# fpga11-serdes-power.net
KiCad netlist of a schematic drawn in Altium Designer
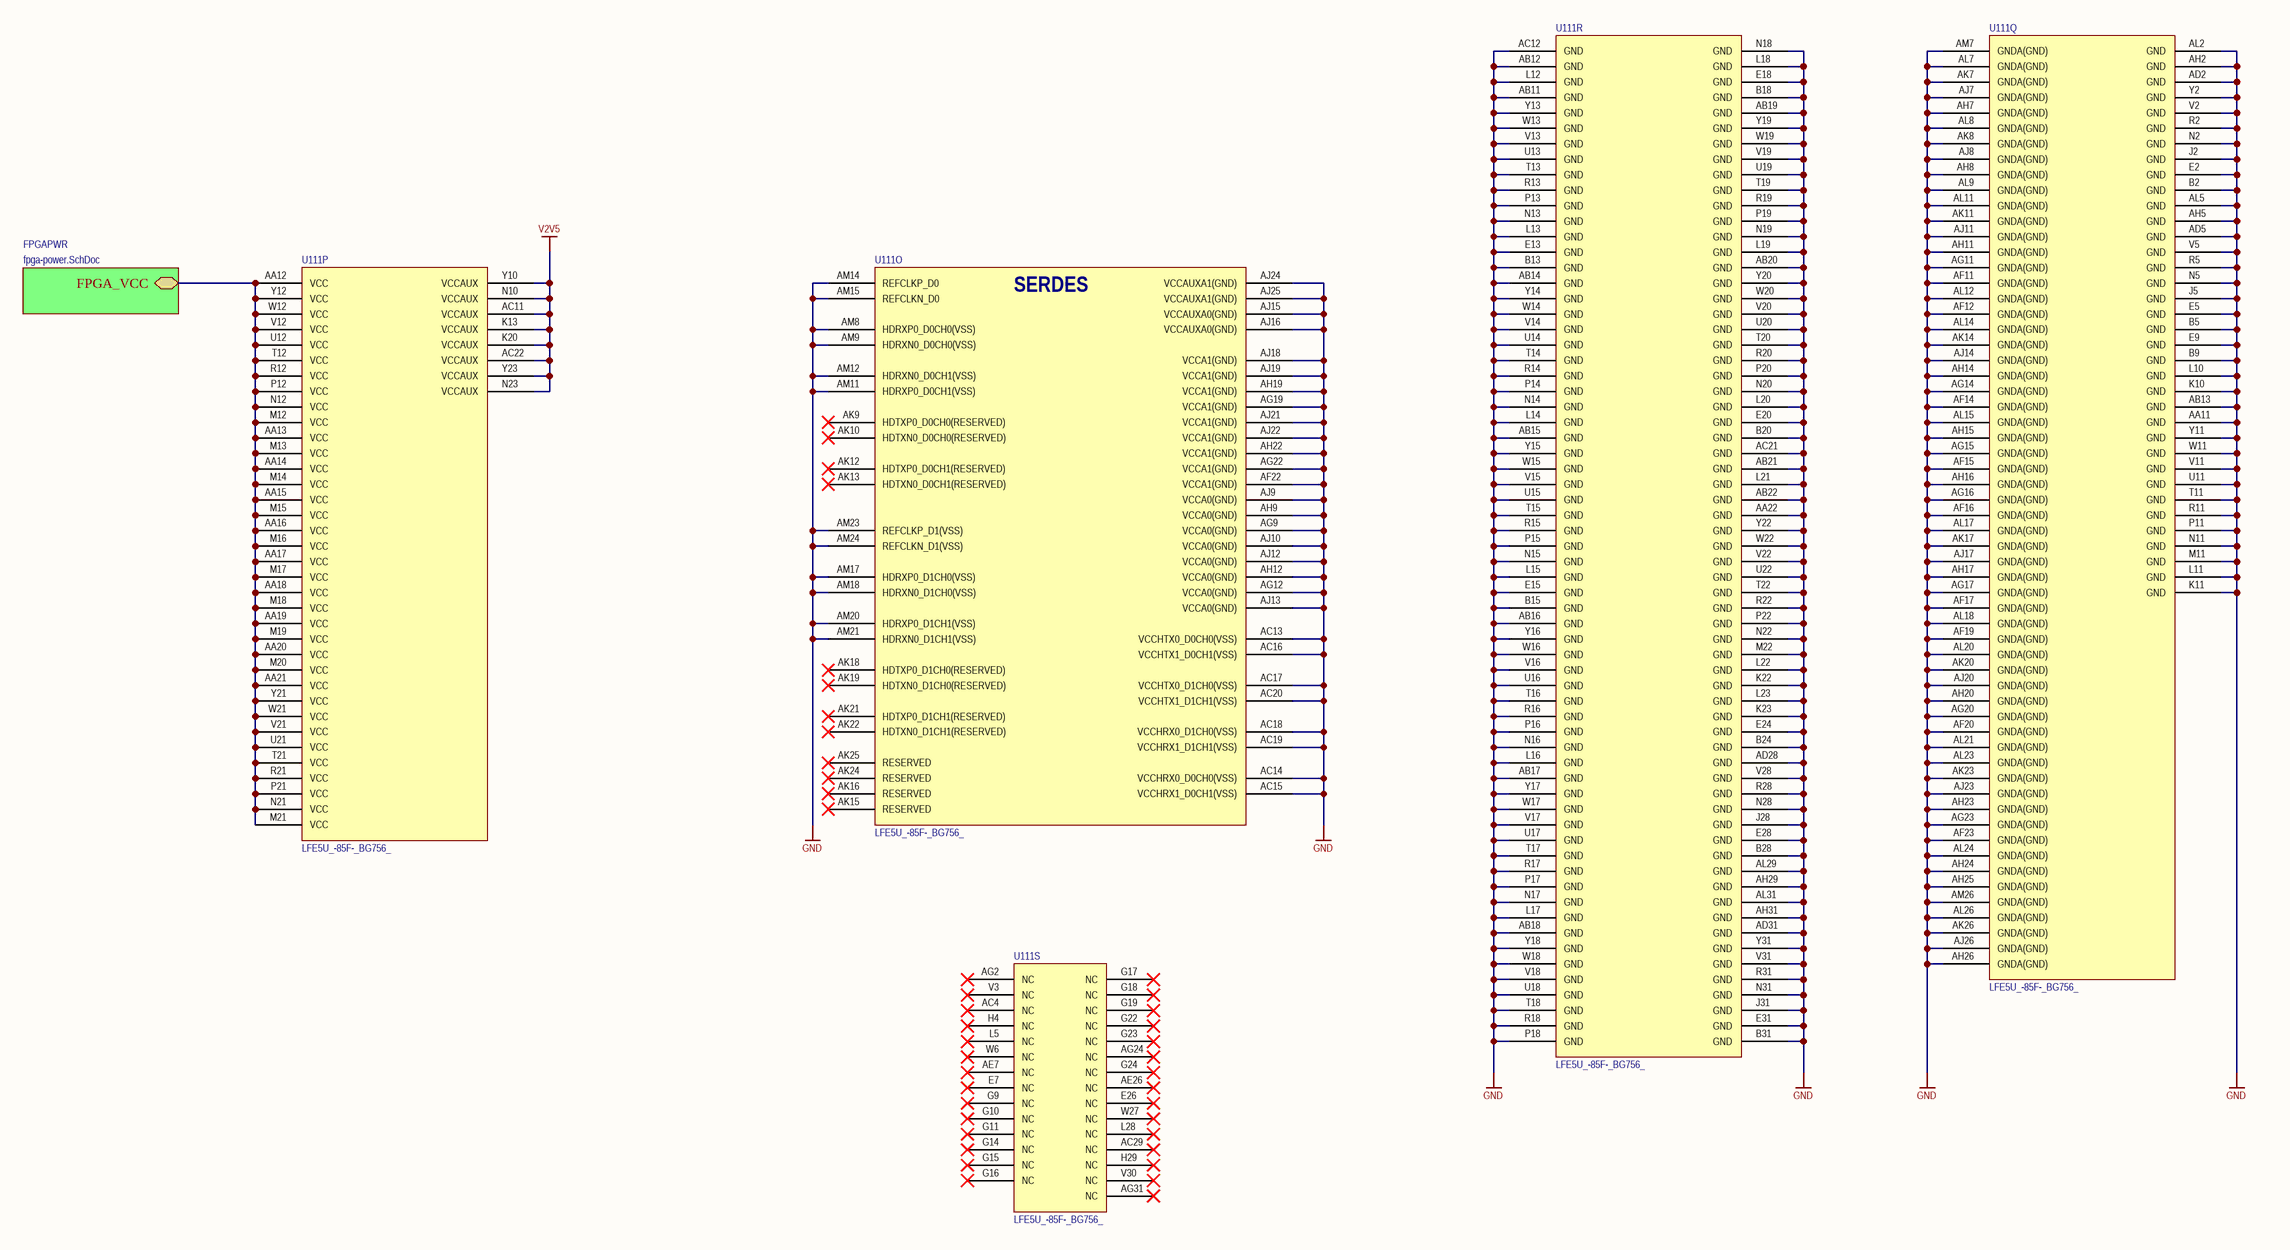
[diagram p0: fpga11-serdes-power.SchDoc]

(export (version "E")
  (design (tool "Eeschema 10.0.6"))
  (components
    (comp (ref "U111")
      (value "LFE5U_-85F-_BG756_")
      (footprint "lattice:caBGA756")
      (description "ECP5 FPGA, 85k LUT, 756-caBGA")
      (fields (field (name "MANUFACTURER") "Lattice Semiconductor"))
      (libsource (lib "lattice") (part "LFE5U_-85F-_BG756_"))
    )
  )
  (nets
    (net (code "1") (name "/FPGA_VCC") (class "Default")
      (node (ref "U111") (pin "AA12") (pinfunction "VCC_AA12") (pintype "power_in"))
      (node (ref "U111") (pin "AA13") (pinfunction "VCC_AA13") (pintype "power_in"))
      (node (ref "U111") (pin "AA14") (pinfunction "VCC_AA14") (pintype "power_in"))
      (node (ref "U111") (pin "AA15") (pinfunction "VCC_AA15") (pintype "power_in"))
      (node (ref "U111") (pin "AA16") (pinfunction "VCC_AA16") (pintype "power_in"))
      (node (ref "U111") (pin "AA17") (pinfunction "VCC_AA17") (pintype "power_in"))
      (node (ref "U111") (pin "AA18") (pinfunction "VCC_AA18") (pintype "power_in"))
      (node (ref "U111") (pin "AA19") (pinfunction "VCC_AA19") (pintype "power_in"))
      (node (ref "U111") (pin "AA20") (pinfunction "VCC_AA20") (pintype "power_in"))
      (node (ref "U111") (pin "AA21") (pinfunction "VCC_AA21") (pintype "power_in"))
      (node (ref "U111") (pin "M12") (pinfunction "VCC_M12") (pintype "power_in"))
      (node (ref "U111") (pin "M13") (pinfunction "VCC_M13") (pintype "power_in"))
      (node (ref "U111") (pin "M14") (pinfunction "VCC_M14") (pintype "power_in"))
      (node (ref "U111") (pin "M15") (pinfunction "VCC_M15") (pintype "power_in"))
      (node (ref "U111") (pin "M16") (pinfunction "VCC_M16") (pintype "power_in"))
      (node (ref "U111") (pin "M17") (pinfunction "VCC_M17") (pintype "power_in"))
      (node (ref "U111") (pin "M18") (pinfunction "VCC_M18") (pintype "power_in"))
      (node (ref "U111") (pin "M19") (pinfunction "VCC_M19") (pintype "power_in"))
      (node (ref "U111") (pin "M20") (pinfunction "VCC_M20") (pintype "power_in"))
      (node (ref "U111") (pin "M21") (pinfunction "VCC_M21") (pintype "power_in"))
      (node (ref "U111") (pin "N12") (pinfunction "VCC_N12") (pintype "power_in"))
      (node (ref "U111") (pin "N21") (pinfunction "VCC_N21") (pintype "power_in"))
      (node (ref "U111") (pin "P12") (pinfunction "VCC_P12") (pintype "power_in"))
      (node (ref "U111") (pin "P21") (pinfunction "VCC_P21") (pintype "power_in"))
      (node (ref "U111") (pin "R12") (pinfunction "VCC_R12") (pintype "power_in"))
      (node (ref "U111") (pin "R21") (pinfunction "VCC_R21") (pintype "power_in"))
      (node (ref "U111") (pin "T12") (pinfunction "VCC_T12") (pintype "power_in"))
      (node (ref "U111") (pin "T21") (pinfunction "VCC_T21") (pintype "power_in"))
      (node (ref "U111") (pin "U12") (pinfunction "VCC_U12") (pintype "power_in"))
      (node (ref "U111") (pin "U21") (pinfunction "VCC_U21") (pintype "power_in"))
      (node (ref "U111") (pin "V12") (pinfunction "VCC_V12") (pintype "power_in"))
      (node (ref "U111") (pin "V21") (pinfunction "VCC_V21") (pintype "power_in"))
      (node (ref "U111") (pin "W12") (pinfunction "VCC_W12") (pintype "power_in"))
      (node (ref "U111") (pin "W21") (pinfunction "VCC_W21") (pintype "power_in"))
      (node (ref "U111") (pin "Y12") (pinfunction "VCC_Y12") (pintype "power_in"))
      (node (ref "U111") (pin "Y21") (pinfunction "VCC_Y21") (pintype "power_in"))
    )
    (net (code "2") (name "GND") (class "Default")
      (node (ref "U111") (pin "AA11") (pinfunction "GND_AA11") (pintype "power_in"))
      (node (ref "U111") (pin "AA22") (pinfunction "GND_AA22") (pintype "power_in"))
      (node (ref "U111") (pin "AB11") (pinfunction "GND_AB11") (pintype "power_in"))
      (node (ref "U111") (pin "AB12") (pinfunction "GND_AB12") (pintype "power_in"))
      (node (ref "U111") (pin "AB13") (pinfunction "GND_AB13") (pintype "power_in"))
      (node (ref "U111") (pin "AB14") (pinfunction "GND_AB14") (pintype "power_in"))
      (node (ref "U111") (pin "AB15") (pinfunction "GND_AB15") (pintype "power_in"))
      (node (ref "U111") (pin "AB16") (pinfunction "GND_AB16") (pintype "power_in"))
      (node (ref "U111") (pin "AB17") (pinfunction "GND_AB17") (pintype "power_in"))
      (node (ref "U111") (pin "AB18") (pinfunction "GND_AB18") (pintype "power_in"))
      (node (ref "U111") (pin "AB19") (pinfunction "GND_AB19") (pintype "power_in"))
      (node (ref "U111") (pin "AB20") (pinfunction "GND_AB20") (pintype "power_in"))
      (node (ref "U111") (pin "AB21") (pinfunction "GND_AB21") (pintype "power_in"))
      (node (ref "U111") (pin "AB22") (pinfunction "GND_AB22") (pintype "power_in"))
      (node (ref "U111") (pin "AC12") (pinfunction "GND_AC12") (pintype "power_in"))
      (node (ref "U111") (pin "AC13") (pinfunction "VCCHTX0_D0CH0(VSS)_AC13") (pintype "power_in"))
      (node (ref "U111") (pin "AC14") (pinfunction "VCCHRX0_D0CH0(VSS)_AC14") (pintype "power_in"))
      (node (ref "U111") (pin "AC15") (pinfunction "VCCHRX1_D0CH1(VSS)_AC15") (pintype "power_in"))
      (node (ref "U111") (pin "AC16") (pinfunction "VCCHTX1_D0CH1(VSS)_AC16") (pintype "power_in"))
      (node (ref "U111") (pin "AC17") (pinfunction "VCCHTX0_D1CH0(VSS)_AC17") (pintype "power_in"))
      (node (ref "U111") (pin "AC18") (pinfunction "VCCHRX0_D1CH0(VSS)_AC18") (pintype "power_in"))
      (node (ref "U111") (pin "AC19") (pinfunction "VCCHRX1_D1CH1(VSS)_AC19") (pintype "power_in"))
      (node (ref "U111") (pin "AC20") (pinfunction "VCCHTX1_D1CH1(VSS)_AC20") (pintype "power_in"))
      (node (ref "U111") (pin "AC21") (pinfunction "GND_AC21") (pintype "power_in"))
      (node (ref "U111") (pin "AD2") (pinfunction "GND_AD2") (pintype "power_in"))
      (node (ref "U111") (pin "AD28") (pinfunction "GND_AD28") (pintype "power_in"))
      (node (ref "U111") (pin "AD31") (pinfunction "GND_AD31") (pintype "power_in"))
      (node (ref "U111") (pin "AD5") (pinfunction "GND_AD5") (pintype "power_in"))
      (node (ref "U111") (pin "AF11") (pinfunction "GNDA(GND)_AF11") (pintype "power_in"))
      (node (ref "U111") (pin "AF12") (pinfunction "GNDA(GND)_AF12") (pintype "power_in"))
      (node (ref "U111") (pin "AF14") (pinfunction "GNDA(GND)_AF14") (pintype "power_in"))
      (node (ref "U111") (pin "AF15") (pinfunction "GNDA(GND)_AF15") (pintype "power_in"))
      (node (ref "U111") (pin "AF16") (pinfunction "GNDA(GND)_AF16") (pintype "power_in"))
      (node (ref "U111") (pin "AF17") (pinfunction "GNDA(GND)_AF17") (pintype "power_in"))
      (node (ref "U111") (pin "AF19") (pinfunction "GNDA(GND)_AF19") (pintype "power_in"))
      (node (ref "U111") (pin "AF20") (pinfunction "GNDA(GND)_AF20") (pintype "power_in"))
      (node (ref "U111") (pin "AF22") (pinfunction "VCCA1(GND)_AF22") (pintype "power_in"))
      (node (ref "U111") (pin "AF23") (pinfunction "GNDA(GND)_AF23") (pintype "power_in"))
      (node (ref "U111") (pin "AG11") (pinfunction "GNDA(GND)_AG11") (pintype "power_in"))
      (node (ref "U111") (pin "AG12") (pinfunction "VCCA0(GND)_AG12") (pintype "power_in"))
      (node (ref "U111") (pin "AG14") (pinfunction "GNDA(GND)_AG14") (pintype "power_in"))
      (node (ref "U111") (pin "AG15") (pinfunction "GNDA(GND)_AG15") (pintype "power_in"))
      (node (ref "U111") (pin "AG16") (pinfunction "GNDA(GND)_AG16") (pintype "power_in"))
      (node (ref "U111") (pin "AG17") (pinfunction "GNDA(GND)_AG17") (pintype "power_in"))
      (node (ref "U111") (pin "AG19") (pinfunction "VCCA1(GND)_AG19") (pintype "power_in"))
      (node (ref "U111") (pin "AG20") (pinfunction "GNDA(GND)_AG20") (pintype "power_in"))
      (node (ref "U111") (pin "AG22") (pinfunction "VCCA1(GND)_AG22") (pintype "power_in"))
      (node (ref "U111") (pin "AG23") (pinfunction "GNDA(GND)_AG23") (pintype "power_in"))
      (node (ref "U111") (pin "AG9") (pinfunction "VCCA0(GND)_AG9") (pintype "power_in"))
      (node (ref "U111") (pin "AH11") (pinfunction "GNDA(GND)_AH11") (pintype "power_in"))
      (node (ref "U111") (pin "AH12") (pinfunction "VCCA0(GND)_AH12") (pintype "power_in"))
      (node (ref "U111") (pin "AH14") (pinfunction "GNDA(GND)_AH14") (pintype "power_in"))
      (node (ref "U111") (pin "AH15") (pinfunction "GNDA(GND)_AH15") (pintype "power_in"))
      (node (ref "U111") (pin "AH16") (pinfunction "GNDA(GND)_AH16") (pintype "power_in"))
      (node (ref "U111") (pin "AH17") (pinfunction "GNDA(GND)_AH17") (pintype "power_in"))
      (node (ref "U111") (pin "AH19") (pinfunction "VCCA1(GND)_AH19") (pintype "power_in"))
      (node (ref "U111") (pin "AH2") (pinfunction "GND_AH2") (pintype "power_in"))
      (node (ref "U111") (pin "AH20") (pinfunction "GNDA(GND)_AH20") (pintype "power_in"))
      (node (ref "U111") (pin "AH22") (pinfunction "VCCA1(GND)_AH22") (pintype "power_in"))
      (node (ref "U111") (pin "AH23") (pinfunction "GNDA(GND)_AH23") (pintype "power_in"))
      (node (ref "U111") (pin "AH24") (pinfunction "GNDA(GND)_AH24") (pintype "power_in"))
      (node (ref "U111") (pin "AH25") (pinfunction "GNDA(GND)_AH25") (pintype "power_in"))
      (node (ref "U111") (pin "AH26") (pinfunction "GNDA(GND)_AH26") (pintype "power_in"))
      (node (ref "U111") (pin "AH29") (pinfunction "GND_AH29") (pintype "power_in"))
      (node (ref "U111") (pin "AH31") (pinfunction "GND_AH31") (pintype "power_in"))
      (node (ref "U111") (pin "AH5") (pinfunction "GND_AH5") (pintype "power_in"))
      (node (ref "U111") (pin "AH7") (pinfunction "GNDA(GND)_AH7") (pintype "power_in"))
      (node (ref "U111") (pin "AH8") (pinfunction "GNDA(GND)_AH8") (pintype "power_in"))
      (node (ref "U111") (pin "AH9") (pinfunction "VCCA0(GND)_AH9") (pintype "power_in"))
      (node (ref "U111") (pin "AJ10") (pinfunction "VCCA0(GND)_AJ10") (pintype "power_in"))
      (node (ref "U111") (pin "AJ11") (pinfunction "GNDA(GND)_AJ11") (pintype "power_in"))
      (node (ref "U111") (pin "AJ12") (pinfunction "VCCA0(GND)_AJ12") (pintype "power_in"))
      (node (ref "U111") (pin "AJ13") (pinfunction "VCCA0(GND)_AJ13") (pintype "power_in"))
      (node (ref "U111") (pin "AJ14") (pinfunction "GNDA(GND)_AJ14") (pintype "power_in"))
      (node (ref "U111") (pin "AJ15") (pinfunction "VCCAUXA0(GND)_AJ15") (pintype "power_in"))
      (node (ref "U111") (pin "AJ16") (pinfunction "VCCAUXA0(GND)_AJ16") (pintype "power_in"))
      (node (ref "U111") (pin "AJ17") (pinfunction "GNDA(GND)_AJ17") (pintype "power_in"))
      (node (ref "U111") (pin "AJ18") (pinfunction "VCCA1(GND)_AJ18") (pintype "power_in"))
      (node (ref "U111") (pin "AJ19") (pinfunction "VCCA1(GND)_AJ19") (pintype "power_in"))
      (node (ref "U111") (pin "AJ20") (pinfunction "GNDA(GND)_AJ20") (pintype "power_in"))
      (node (ref "U111") (pin "AJ21") (pinfunction "VCCA1(GND)_AJ21") (pintype "power_in"))
      (node (ref "U111") (pin "AJ22") (pinfunction "VCCA1(GND)_AJ22") (pintype "power_in"))
      (node (ref "U111") (pin "AJ23") (pinfunction "GNDA(GND)_AJ23") (pintype "power_in"))
      (node (ref "U111") (pin "AJ24") (pinfunction "VCCAUXA1(GND)_AJ24") (pintype "power_in"))
      (node (ref "U111") (pin "AJ25") (pinfunction "VCCAUXA1(GND)_AJ25") (pintype "power_in"))
      (node (ref "U111") (pin "AJ26") (pinfunction "GNDA(GND)_AJ26") (pintype "power_in"))
      (node (ref "U111") (pin "AJ7") (pinfunction "GNDA(GND)_AJ7") (pintype "power_in"))
      (node (ref "U111") (pin "AJ8") (pinfunction "GNDA(GND)_AJ8") (pintype "power_in"))
      (node (ref "U111") (pin "AJ9") (pinfunction "VCCA0(GND)_AJ9") (pintype "power_in"))
      (node (ref "U111") (pin "AK11") (pinfunction "GNDA(GND)_AK11") (pintype "power_in"))
      (node (ref "U111") (pin "AK14") (pinfunction "GNDA(GND)_AK14") (pintype "power_in"))
      (node (ref "U111") (pin "AK17") (pinfunction "GNDA(GND)_AK17") (pintype "power_in"))
      (node (ref "U111") (pin "AK20") (pinfunction "GNDA(GND)_AK20") (pintype "power_in"))
      (node (ref "U111") (pin "AK23") (pinfunction "GNDA(GND)_AK23") (pintype "power_in"))
      (node (ref "U111") (pin "AK26") (pinfunction "GNDA(GND)_AK26") (pintype "power_in"))
      (node (ref "U111") (pin "AK7") (pinfunction "GNDA(GND)_AK7") (pintype "power_in"))
      (node (ref "U111") (pin "AK8") (pinfunction "GNDA(GND)_AK8") (pintype "power_in"))
      (node (ref "U111") (pin "AL11") (pinfunction "GNDA(GND)_AL11") (pintype "power_in"))
      (node (ref "U111") (pin "AL12") (pinfunction "GNDA(GND)_AL12") (pintype "power_in"))
      (node (ref "U111") (pin "AL14") (pinfunction "GNDA(GND)_AL14") (pintype "power_in"))
      (node (ref "U111") (pin "AL15") (pinfunction "GNDA(GND)_AL15") (pintype "power_in"))
      (node (ref "U111") (pin "AL17") (pinfunction "GNDA(GND)_AL17") (pintype "power_in"))
      (node (ref "U111") (pin "AL18") (pinfunction "GNDA(GND)_AL18") (pintype "power_in"))
      (node (ref "U111") (pin "AL2") (pinfunction "GND_AL2") (pintype "power_in"))
      (node (ref "U111") (pin "AL20") (pinfunction "GNDA(GND)_AL20") (pintype "power_in"))
      (node (ref "U111") (pin "AL21") (pinfunction "GNDA(GND)_AL21") (pintype "power_in"))
      (node (ref "U111") (pin "AL23") (pinfunction "GNDA(GND)_AL23") (pintype "power_in"))
      (node (ref "U111") (pin "AL24") (pinfunction "GNDA(GND)_AL24") (pintype "power_in"))
      (node (ref "U111") (pin "AL26") (pinfunction "GNDA(GND)_AL26") (pintype "power_in"))
      (node (ref "U111") (pin "AL29") (pinfunction "GND_AL29") (pintype "power_in"))
      (node (ref "U111") (pin "AL31") (pinfunction "GND_AL31") (pintype "power_in"))
      (node (ref "U111") (pin "AL5") (pinfunction "GND_AL5") (pintype "power_in"))
      (node (ref "U111") (pin "AL7") (pinfunction "GNDA(GND)_AL7") (pintype "power_in"))
      (node (ref "U111") (pin "AL8") (pinfunction "GNDA(GND)_AL8") (pintype "power_in"))
      (node (ref "U111") (pin "AL9") (pinfunction "GNDA(GND)_AL9") (pintype "power_in"))
      (node (ref "U111") (pin "AM11") (pinfunction "HDRXP0_D0CH1(VSS)_AM11") (pintype "passive"))
      (node (ref "U111") (pin "AM12") (pinfunction "HDRXN0_D0CH1(VSS)_AM12") (pintype "passive"))
      (node (ref "U111") (pin "AM14") (pinfunction "REFCLKP_D0_AM14") (pintype "passive"))
      (node (ref "U111") (pin "AM15") (pinfunction "REFCLKN_D0_AM15") (pintype "passive"))
      (node (ref "U111") (pin "AM17") (pinfunction "HDRXP0_D1CH0(VSS)_AM17") (pintype "passive"))
      (node (ref "U111") (pin "AM18") (pinfunction "HDRXN0_D1CH0(VSS)_AM18") (pintype "passive"))
      (node (ref "U111") (pin "AM20") (pinfunction "HDRXP0_D1CH1(VSS)_AM20") (pintype "passive"))
      (node (ref "U111") (pin "AM21") (pinfunction "HDRXN0_D1CH1(VSS)_AM21") (pintype "passive"))
      (node (ref "U111") (pin "AM23") (pinfunction "REFCLKP_D1(VSS)_AM23") (pintype "passive"))
      (node (ref "U111") (pin "AM24") (pinfunction "REFCLKN_D1(VSS)_AM24") (pintype "passive"))
      (node (ref "U111") (pin "AM26") (pinfunction "GNDA(GND)_AM26") (pintype "power_in"))
      (node (ref "U111") (pin "AM7") (pinfunction "GNDA(GND)_AM7") (pintype "power_in"))
      (node (ref "U111") (pin "AM8") (pinfunction "HDRXP0_D0CH0(VSS)_AM8") (pintype "passive"))
      (node (ref "U111") (pin "AM9") (pinfunction "HDRXN0_D0CH0(VSS)_AM9") (pintype "passive"))
      (node (ref "U111") (pin "B13") (pinfunction "GND_B13") (pintype "power_in"))
      (node (ref "U111") (pin "B15") (pinfunction "GND_B15") (pintype "power_in"))
      (node (ref "U111") (pin "B18") (pinfunction "GND_B18") (pintype "power_in"))
      (node (ref "U111") (pin "B2") (pinfunction "GND_B2") (pintype "power_in"))
      (node (ref "U111") (pin "B20") (pinfunction "GND_B20") (pintype "power_in"))
      (node (ref "U111") (pin "B24") (pinfunction "GND_B24") (pintype "power_in"))
      (node (ref "U111") (pin "B28") (pinfunction "GND_B28") (pintype "power_in"))
      (node (ref "U111") (pin "B31") (pinfunction "GND_B31") (pintype "power_in"))
      (node (ref "U111") (pin "B5") (pinfunction "GND_B5") (pintype "power_in"))
      (node (ref "U111") (pin "B9") (pinfunction "GND_B9") (pintype "power_in"))
      (node (ref "U111") (pin "E13") (pinfunction "GND_E13") (pintype "power_in"))
      (node (ref "U111") (pin "E15") (pinfunction "GND_E15") (pintype "power_in"))
      (node (ref "U111") (pin "E18") (pinfunction "GND_E18") (pintype "power_in"))
      (node (ref "U111") (pin "E2") (pinfunction "GND_E2") (pintype "power_in"))
      (node (ref "U111") (pin "E20") (pinfunction "GND_E20") (pintype "power_in"))
      (node (ref "U111") (pin "E24") (pinfunction "GND_E24") (pintype "power_in"))
      (node (ref "U111") (pin "E28") (pinfunction "GND_E28") (pintype "power_in"))
      (node (ref "U111") (pin "E31") (pinfunction "GND_E31") (pintype "power_in"))
      (node (ref "U111") (pin "E5") (pinfunction "GND_E5") (pintype "power_in"))
      (node (ref "U111") (pin "E9") (pinfunction "GND_E9") (pintype "power_in"))
      (node (ref "U111") (pin "J2") (pinfunction "GND_J2") (pintype "power_in"))
      (node (ref "U111") (pin "J28") (pinfunction "GND_J28") (pintype "power_in"))
      (node (ref "U111") (pin "J31") (pinfunction "GND_J31") (pintype "power_in"))
      (node (ref "U111") (pin "J5") (pinfunction "GND_J5") (pintype "power_in"))
      (node (ref "U111") (pin "K10") (pinfunction "GND_K10") (pintype "power_in"))
      (node (ref "U111") (pin "K11") (pinfunction "GND_K11") (pintype "power_in"))
      (node (ref "U111") (pin "K22") (pinfunction "GND_K22") (pintype "power_in"))
      (node (ref "U111") (pin "K23") (pinfunction "GND_K23") (pintype "power_in"))
      (node (ref "U111") (pin "L10") (pinfunction "GND_L10") (pintype "power_in"))
      (node (ref "U111") (pin "L11") (pinfunction "GND_L11") (pintype "power_in"))
      (node (ref "U111") (pin "L12") (pinfunction "GND_L12") (pintype "power_in"))
      (node (ref "U111") (pin "L13") (pinfunction "GND_L13") (pintype "power_in"))
      (node (ref "U111") (pin "L14") (pinfunction "GND_L14") (pintype "power_in"))
      (node (ref "U111") (pin "L15") (pinfunction "GND_L15") (pintype "power_in"))
      (node (ref "U111") (pin "L16") (pinfunction "GND_L16") (pintype "power_in"))
      (node (ref "U111") (pin "L17") (pinfunction "GND_L17") (pintype "power_in"))
      (node (ref "U111") (pin "L18") (pinfunction "GND_L18") (pintype "power_in"))
      (node (ref "U111") (pin "L19") (pinfunction "GND_L19") (pintype "power_in"))
      (node (ref "U111") (pin "L20") (pinfunction "GND_L20") (pintype "power_in"))
      (node (ref "U111") (pin "L21") (pinfunction "GND_L21") (pintype "power_in"))
      (node (ref "U111") (pin "L22") (pinfunction "GND_L22") (pintype "power_in"))
      (node (ref "U111") (pin "L23") (pinfunction "GND_L23") (pintype "power_in"))
      (node (ref "U111") (pin "M11") (pinfunction "GND_M11") (pintype "power_in"))
      (node (ref "U111") (pin "M22") (pinfunction "GND_M22") (pintype "power_in"))
      (node (ref "U111") (pin "N11") (pinfunction "GND_N11") (pintype "power_in"))
      (node (ref "U111") (pin "N13") (pinfunction "GND_N13") (pintype "power_in"))
      (node (ref "U111") (pin "N14") (pinfunction "GND_N14") (pintype "power_in"))
      (node (ref "U111") (pin "N15") (pinfunction "GND_N15") (pintype "power_in"))
      (node (ref "U111") (pin "N16") (pinfunction "GND_N16") (pintype "power_in"))
      (node (ref "U111") (pin "N17") (pinfunction "GND_N17") (pintype "power_in"))
      (node (ref "U111") (pin "N18") (pinfunction "GND_N18") (pintype "power_in"))
      (node (ref "U111") (pin "N19") (pinfunction "GND_N19") (pintype "power_in"))
      (node (ref "U111") (pin "N2") (pinfunction "GND_N2") (pintype "power_in"))
      (node (ref "U111") (pin "N20") (pinfunction "GND_N20") (pintype "power_in"))
      (node (ref "U111") (pin "N22") (pinfunction "GND_N22") (pintype "power_in"))
      (node (ref "U111") (pin "N28") (pinfunction "GND_N28") (pintype "power_in"))
      (node (ref "U111") (pin "N31") (pinfunction "GND_N31") (pintype "power_in"))
      (node (ref "U111") (pin "N5") (pinfunction "GND_N5") (pintype "power_in"))
      (node (ref "U111") (pin "P11") (pinfunction "GND_P11") (pintype "power_in"))
      (node (ref "U111") (pin "P13") (pinfunction "GND_P13") (pintype "power_in"))
      (node (ref "U111") (pin "P14") (pinfunction "GND_P14") (pintype "power_in"))
      (node (ref "U111") (pin "P15") (pinfunction "GND_P15") (pintype "power_in"))
      (node (ref "U111") (pin "P16") (pinfunction "GND_P16") (pintype "power_in"))
      (node (ref "U111") (pin "P17") (pinfunction "GND_P17") (pintype "power_in"))
      (node (ref "U111") (pin "P18") (pinfunction "GND_P18") (pintype "power_in"))
      (node (ref "U111") (pin "P19") (pinfunction "GND_P19") (pintype "power_in"))
      (node (ref "U111") (pin "P20") (pinfunction "GND_P20") (pintype "power_in"))
      (node (ref "U111") (pin "P22") (pinfunction "GND_P22") (pintype "power_in"))
      (node (ref "U111") (pin "R11") (pinfunction "GND_R11") (pintype "power_in"))
      (node (ref "U111") (pin "R13") (pinfunction "GND_R13") (pintype "power_in"))
      (node (ref "U111") (pin "R14") (pinfunction "GND_R14") (pintype "power_in"))
      (node (ref "U111") (pin "R15") (pinfunction "GND_R15") (pintype "power_in"))
      (node (ref "U111") (pin "R16") (pinfunction "GND_R16") (pintype "power_in"))
      (node (ref "U111") (pin "R17") (pinfunction "GND_R17") (pintype "power_in"))
      (node (ref "U111") (pin "R18") (pinfunction "GND_R18") (pintype "power_in"))
      (node (ref "U111") (pin "R19") (pinfunction "GND_R19") (pintype "power_in"))
      (node (ref "U111") (pin "R2") (pinfunction "GND_R2") (pintype "power_in"))
      (node (ref "U111") (pin "R20") (pinfunction "GND_R20") (pintype "power_in"))
      (node (ref "U111") (pin "R22") (pinfunction "GND_R22") (pintype "power_in"))
      (node (ref "U111") (pin "R28") (pinfunction "GND_R28") (pintype "power_in"))
      (node (ref "U111") (pin "R31") (pinfunction "GND_R31") (pintype "power_in"))
      (node (ref "U111") (pin "R5") (pinfunction "GND_R5") (pintype "power_in"))
      (node (ref "U111") (pin "T11") (pinfunction "GND_T11") (pintype "power_in"))
      (node (ref "U111") (pin "T13") (pinfunction "GND_T13") (pintype "power_in"))
      (node (ref "U111") (pin "T14") (pinfunction "GND_T14") (pintype "power_in"))
      (node (ref "U111") (pin "T15") (pinfunction "GND_T15") (pintype "power_in"))
      (node (ref "U111") (pin "T16") (pinfunction "GND_T16") (pintype "power_in"))
      (node (ref "U111") (pin "T17") (pinfunction "GND_T17") (pintype "power_in"))
      (node (ref "U111") (pin "T18") (pinfunction "GND_T18") (pintype "power_in"))
      (node (ref "U111") (pin "T19") (pinfunction "GND_T19") (pintype "power_in"))
      (node (ref "U111") (pin "T20") (pinfunction "GND_T20") (pintype "power_in"))
      (node (ref "U111") (pin "T22") (pinfunction "GND_T22") (pintype "power_in"))
      (node (ref "U111") (pin "U11") (pinfunction "GND_U11") (pintype "power_in"))
      (node (ref "U111") (pin "U13") (pinfunction "GND_U13") (pintype "power_in"))
      (node (ref "U111") (pin "U14") (pinfunction "GND_U14") (pintype "power_in"))
      (node (ref "U111") (pin "U15") (pinfunction "GND_U15") (pintype "power_in"))
      (node (ref "U111") (pin "U16") (pinfunction "GND_U16") (pintype "power_in"))
      (node (ref "U111") (pin "U17") (pinfunction "GND_U17") (pintype "power_in"))
      (node (ref "U111") (pin "U18") (pinfunction "GND_U18") (pintype "power_in"))
      (node (ref "U111") (pin "U19") (pinfunction "GND_U19") (pintype "power_in"))
      (node (ref "U111") (pin "U20") (pinfunction "GND_U20") (pintype "power_in"))
      (node (ref "U111") (pin "U22") (pinfunction "GND_U22") (pintype "power_in"))
      (node (ref "U111") (pin "V11") (pinfunction "GND_V11") (pintype "power_in"))
      (node (ref "U111") (pin "V13") (pinfunction "GND_V13") (pintype "power_in"))
      (node (ref "U111") (pin "V14") (pinfunction "GND_V14") (pintype "power_in"))
      (node (ref "U111") (pin "V15") (pinfunction "GND_V15") (pintype "power_in"))
      (node (ref "U111") (pin "V16") (pinfunction "GND_V16") (pintype "power_in"))
      (node (ref "U111") (pin "V17") (pinfunction "GND_V17") (pintype "power_in"))
      (node (ref "U111") (pin "V18") (pinfunction "GND_V18") (pintype "power_in"))
      (node (ref "U111") (pin "V19") (pinfunction "GND_V19") (pintype "power_in"))
      (node (ref "U111") (pin "V2") (pinfunction "GND_V2") (pintype "power_in"))
      (node (ref "U111") (pin "V20") (pinfunction "GND_V20") (pintype "power_in"))
      (node (ref "U111") (pin "V22") (pinfunction "GND_V22") (pintype "power_in"))
      (node (ref "U111") (pin "V28") (pinfunction "GND_V28") (pintype "power_in"))
      (node (ref "U111") (pin "V31") (pinfunction "GND_V31") (pintype "power_in"))
      (node (ref "U111") (pin "V5") (pinfunction "GND_V5") (pintype "power_in"))
      (node (ref "U111") (pin "W11") (pinfunction "GND_W11") (pintype "power_in"))
      (node (ref "U111") (pin "W13") (pinfunction "GND_W13") (pintype "power_in"))
      (node (ref "U111") (pin "W14") (pinfunction "GND_W14") (pintype "power_in"))
      (node (ref "U111") (pin "W15") (pinfunction "GND_W15") (pintype "power_in"))
      (node (ref "U111") (pin "W16") (pinfunction "GND_W16") (pintype "power_in"))
      (node (ref "U111") (pin "W17") (pinfunction "GND_W17") (pintype "power_in"))
      (node (ref "U111") (pin "W18") (pinfunction "GND_W18") (pintype "power_in"))
      (node (ref "U111") (pin "W19") (pinfunction "GND_W19") (pintype "power_in"))
      (node (ref "U111") (pin "W20") (pinfunction "GND_W20") (pintype "power_in"))
      (node (ref "U111") (pin "W22") (pinfunction "GND_W22") (pintype "power_in"))
      (node (ref "U111") (pin "Y11") (pinfunction "GND_Y11") (pintype "power_in"))
      (node (ref "U111") (pin "Y13") (pinfunction "GND_Y13") (pintype "power_in"))
      (node (ref "U111") (pin "Y14") (pinfunction "GND_Y14") (pintype "power_in"))
      (node (ref "U111") (pin "Y15") (pinfunction "GND_Y15") (pintype "power_in"))
      (node (ref "U111") (pin "Y16") (pinfunction "GND_Y16") (pintype "power_in"))
      (node (ref "U111") (pin "Y17") (pinfunction "GND_Y17") (pintype "power_in"))
      (node (ref "U111") (pin "Y18") (pinfunction "GND_Y18") (pintype "power_in"))
      (node (ref "U111") (pin "Y19") (pinfunction "GND_Y19") (pintype "power_in"))
      (node (ref "U111") (pin "Y2") (pinfunction "GND_Y2") (pintype "power_in"))
      (node (ref "U111") (pin "Y20") (pinfunction "GND_Y20") (pintype "power_in"))
      (node (ref "U111") (pin "Y22") (pinfunction "GND_Y22") (pintype "power_in"))
      (node (ref "U111") (pin "Y31") (pinfunction "GND_Y31") (pintype "power_in"))
    )
    (net (code "3") (name "V2V5") (class "Default")
      (node (ref "U111") (pin "AC11") (pinfunction "VCCAUX_AC11") (pintype "power_in"))
      (node (ref "U111") (pin "AC22") (pinfunction "VCCAUX_AC22") (pintype "power_in"))
      (node (ref "U111") (pin "K13") (pinfunction "VCCAUX_K13") (pintype "power_in"))
      (node (ref "U111") (pin "K20") (pinfunction "VCCAUX_K20") (pintype "power_in"))
      (node (ref "U111") (pin "N10") (pinfunction "VCCAUX_N10") (pintype "power_in"))
      (node (ref "U111") (pin "N23") (pinfunction "VCCAUX_N23") (pintype "power_in"))
      (node (ref "U111") (pin "Y10") (pinfunction "VCCAUX_Y10") (pintype "power_in"))
      (node (ref "U111") (pin "Y23") (pinfunction "VCCAUX_Y23") (pintype "power_in"))
    )
    (net (code "4") (name "unconnected-(U111O-HDTXN0_D0CH0(RESERVED)-PadAK10)") (class "Default")
      (node (ref "U111") (pin "AK10") (pinfunction "HDTXN0_D0CH0(RESERVED)_AK10") (pintype "passive+no_connect"))
    )
    (net (code "5") (name "unconnected-(U111O-HDTXN0_D0CH1(RESERVED)-PadAK13)") (class "Default")
      (node (ref "U111") (pin "AK13") (pinfunction "HDTXN0_D0CH1(RESERVED)_AK13") (pintype "passive+no_connect"))
    )
    (net (code "6") (name "unconnected-(U111O-HDTXN0_D1CH0(RESERVED)-PadAK19)") (class "Default")
      (node (ref "U111") (pin "AK19") (pinfunction "HDTXN0_D1CH0(RESERVED)_AK19") (pintype "passive+no_connect"))
    )
    (net (code "7") (name "unconnected-(U111O-HDTXN0_D1CH1(RESERVED)-PadAK22)") (class "Default")
      (node (ref "U111") (pin "AK22") (pinfunction "HDTXN0_D1CH1(RESERVED)_AK22") (pintype "passive+no_connect"))
    )
    (net (code "8") (name "unconnected-(U111O-HDTXP0_D0CH0(RESERVED)-PadAK9)") (class "Default")
      (node (ref "U111") (pin "AK9") (pinfunction "HDTXP0_D0CH0(RESERVED)_AK9") (pintype "passive+no_connect"))
    )
    (net (code "9") (name "unconnected-(U111O-HDTXP0_D0CH1(RESERVED)-PadAK12)") (class "Default")
      (node (ref "U111") (pin "AK12") (pinfunction "HDTXP0_D0CH1(RESERVED)_AK12") (pintype "passive+no_connect"))
    )
    (net (code "10") (name "unconnected-(U111O-HDTXP0_D1CH0(RESERVED)-PadAK18)") (class "Default")
      (node (ref "U111") (pin "AK18") (pinfunction "HDTXP0_D1CH0(RESERVED)_AK18") (pintype "passive+no_connect"))
    )
    (net (code "11") (name "unconnected-(U111O-HDTXP0_D1CH1(RESERVED)-PadAK21)") (class "Default")
      (node (ref "U111") (pin "AK21") (pinfunction "HDTXP0_D1CH1(RESERVED)_AK21") (pintype "passive+no_connect"))
    )
    (net (code "12") (name "unconnected-(U111O-RESERVED-PadAK15)") (class "Default")
      (node (ref "U111") (pin "AK15") (pinfunction "RESERVED_AK15") (pintype "passive+no_connect"))
    )
    (net (code "13") (name "unconnected-(U111O-RESERVED-PadAK16)") (class "Default")
      (node (ref "U111") (pin "AK16") (pinfunction "RESERVED_AK16") (pintype "passive+no_connect"))
    )
    (net (code "14") (name "unconnected-(U111O-RESERVED-PadAK24)") (class "Default")
      (node (ref "U111") (pin "AK24") (pinfunction "RESERVED_AK24") (pintype "passive+no_connect"))
    )
    (net (code "15") (name "unconnected-(U111O-RESERVED-PadAK25)") (class "Default")
      (node (ref "U111") (pin "AK25") (pinfunction "RESERVED_AK25") (pintype "passive+no_connect"))
    )
    (net (code "16") (name "unconnected-(U111S-NC-PadAC4)") (class "Default")
      (node (ref "U111") (pin "AC4") (pinfunction "NC_AC4") (pintype "passive+no_connect"))
    )
    (net (code "17") (name "unconnected-(U111S-NC-PadAC29)") (class "Default")
      (node (ref "U111") (pin "AC29") (pinfunction "NC_AC29") (pintype "passive+no_connect"))
    )
    (net (code "18") (name "unconnected-(U111S-NC-PadAE7)") (class "Default")
      (node (ref "U111") (pin "AE7") (pinfunction "NC_AE7") (pintype "passive+no_connect"))
    )
    (net (code "19") (name "unconnected-(U111S-NC-PadAE26)") (class "Default")
      (node (ref "U111") (pin "AE26") (pinfunction "NC_AE26") (pintype "passive+no_connect"))
    )
    (net (code "20") (name "unconnected-(U111S-NC-PadAG2)") (class "Default")
      (node (ref "U111") (pin "AG2") (pinfunction "NC_AG2") (pintype "passive+no_connect"))
    )
    (net (code "21") (name "unconnected-(U111S-NC-PadAG24)") (class "Default")
      (node (ref "U111") (pin "AG24") (pinfunction "NC_AG24") (pintype "passive+no_connect"))
    )
    (net (code "22") (name "unconnected-(U111S-NC-PadAG31)") (class "Default")
      (node (ref "U111") (pin "AG31") (pinfunction "NC_AG31") (pintype "passive+no_connect"))
    )
    (net (code "23") (name "unconnected-(U111S-NC-PadE7)") (class "Default")
      (node (ref "U111") (pin "E7") (pinfunction "NC_E7") (pintype "passive+no_connect"))
    )
    (net (code "24") (name "unconnected-(U111S-NC-PadE26)") (class "Default")
      (node (ref "U111") (pin "E26") (pinfunction "NC_E26") (pintype "passive+no_connect"))
    )
    (net (code "25") (name "unconnected-(U111S-NC-PadG9)") (class "Default")
      (node (ref "U111") (pin "G9") (pinfunction "NC_G9") (pintype "passive+no_connect"))
    )
    (net (code "26") (name "unconnected-(U111S-NC-PadG10)") (class "Default")
      (node (ref "U111") (pin "G10") (pinfunction "NC_G10") (pintype "passive+no_connect"))
    )
    (net (code "27") (name "unconnected-(U111S-NC-PadG11)") (class "Default")
      (node (ref "U111") (pin "G11") (pinfunction "NC_G11") (pintype "passive+no_connect"))
    )
    (net (code "28") (name "unconnected-(U111S-NC-PadG14)") (class "Default")
      (node (ref "U111") (pin "G14") (pinfunction "NC_G14") (pintype "passive+no_connect"))
    )
    (net (code "29") (name "unconnected-(U111S-NC-PadG15)") (class "Default")
      (node (ref "U111") (pin "G15") (pinfunction "NC_G15") (pintype "passive+no_connect"))
    )
    (net (code "30") (name "unconnected-(U111S-NC-PadG16)") (class "Default")
      (node (ref "U111") (pin "G16") (pinfunction "NC_G16") (pintype "passive+no_connect"))
    )
    (net (code "31") (name "unconnected-(U111S-NC-PadG17)") (class "Default")
      (node (ref "U111") (pin "G17") (pinfunction "NC_G17") (pintype "passive+no_connect"))
    )
    (net (code "32") (name "unconnected-(U111S-NC-PadG18)") (class "Default")
      (node (ref "U111") (pin "G18") (pinfunction "NC_G18") (pintype "passive+no_connect"))
    )
    (net (code "33") (name "unconnected-(U111S-NC-PadG19)") (class "Default")
      (node (ref "U111") (pin "G19") (pinfunction "NC_G19") (pintype "passive+no_connect"))
    )
    (net (code "34") (name "unconnected-(U111S-NC-PadG22)") (class "Default")
      (node (ref "U111") (pin "G22") (pinfunction "NC_G22") (pintype "passive+no_connect"))
    )
    (net (code "35") (name "unconnected-(U111S-NC-PadG23)") (class "Default")
      (node (ref "U111") (pin "G23") (pinfunction "NC_G23") (pintype "passive+no_connect"))
    )
    (net (code "36") (name "unconnected-(U111S-NC-PadG24)") (class "Default")
      (node (ref "U111") (pin "G24") (pinfunction "NC_G24") (pintype "passive+no_connect"))
    )
    (net (code "37") (name "unconnected-(U111S-NC-PadH4)") (class "Default")
      (node (ref "U111") (pin "H4") (pinfunction "NC_H4") (pintype "passive+no_connect"))
    )
    (net (code "38") (name "unconnected-(U111S-NC-PadH29)") (class "Default")
      (node (ref "U111") (pin "H29") (pinfunction "NC_H29") (pintype "passive+no_connect"))
    )
    (net (code "39") (name "unconnected-(U111S-NC-PadL5)") (class "Default")
      (node (ref "U111") (pin "L5") (pinfunction "NC_L5") (pintype "passive+no_connect"))
    )
    (net (code "40") (name "unconnected-(U111S-NC-PadL28)") (class "Default")
      (node (ref "U111") (pin "L28") (pinfunction "NC_L28") (pintype "passive+no_connect"))
    )
    (net (code "41") (name "unconnected-(U111S-NC-PadV3)") (class "Default")
      (node (ref "U111") (pin "V3") (pinfunction "NC_V3") (pintype "passive+no_connect"))
    )
    (net (code "42") (name "unconnected-(U111S-NC-PadV30)") (class "Default")
      (node (ref "U111") (pin "V30") (pinfunction "NC_V30") (pintype "passive+no_connect"))
    )
    (net (code "43") (name "unconnected-(U111S-NC-PadW6)") (class "Default")
      (node (ref "U111") (pin "W6") (pinfunction "NC_W6") (pintype "passive+no_connect"))
    )
    (net (code "44") (name "unconnected-(U111S-NC-PadW27)") (class "Default")
      (node (ref "U111") (pin "W27") (pinfunction "NC_W27") (pintype "passive+no_connect"))
    )
  )
)
